# Swiip_REV_A1.net
KiCad netlist of a schematic drawn in EAGLE
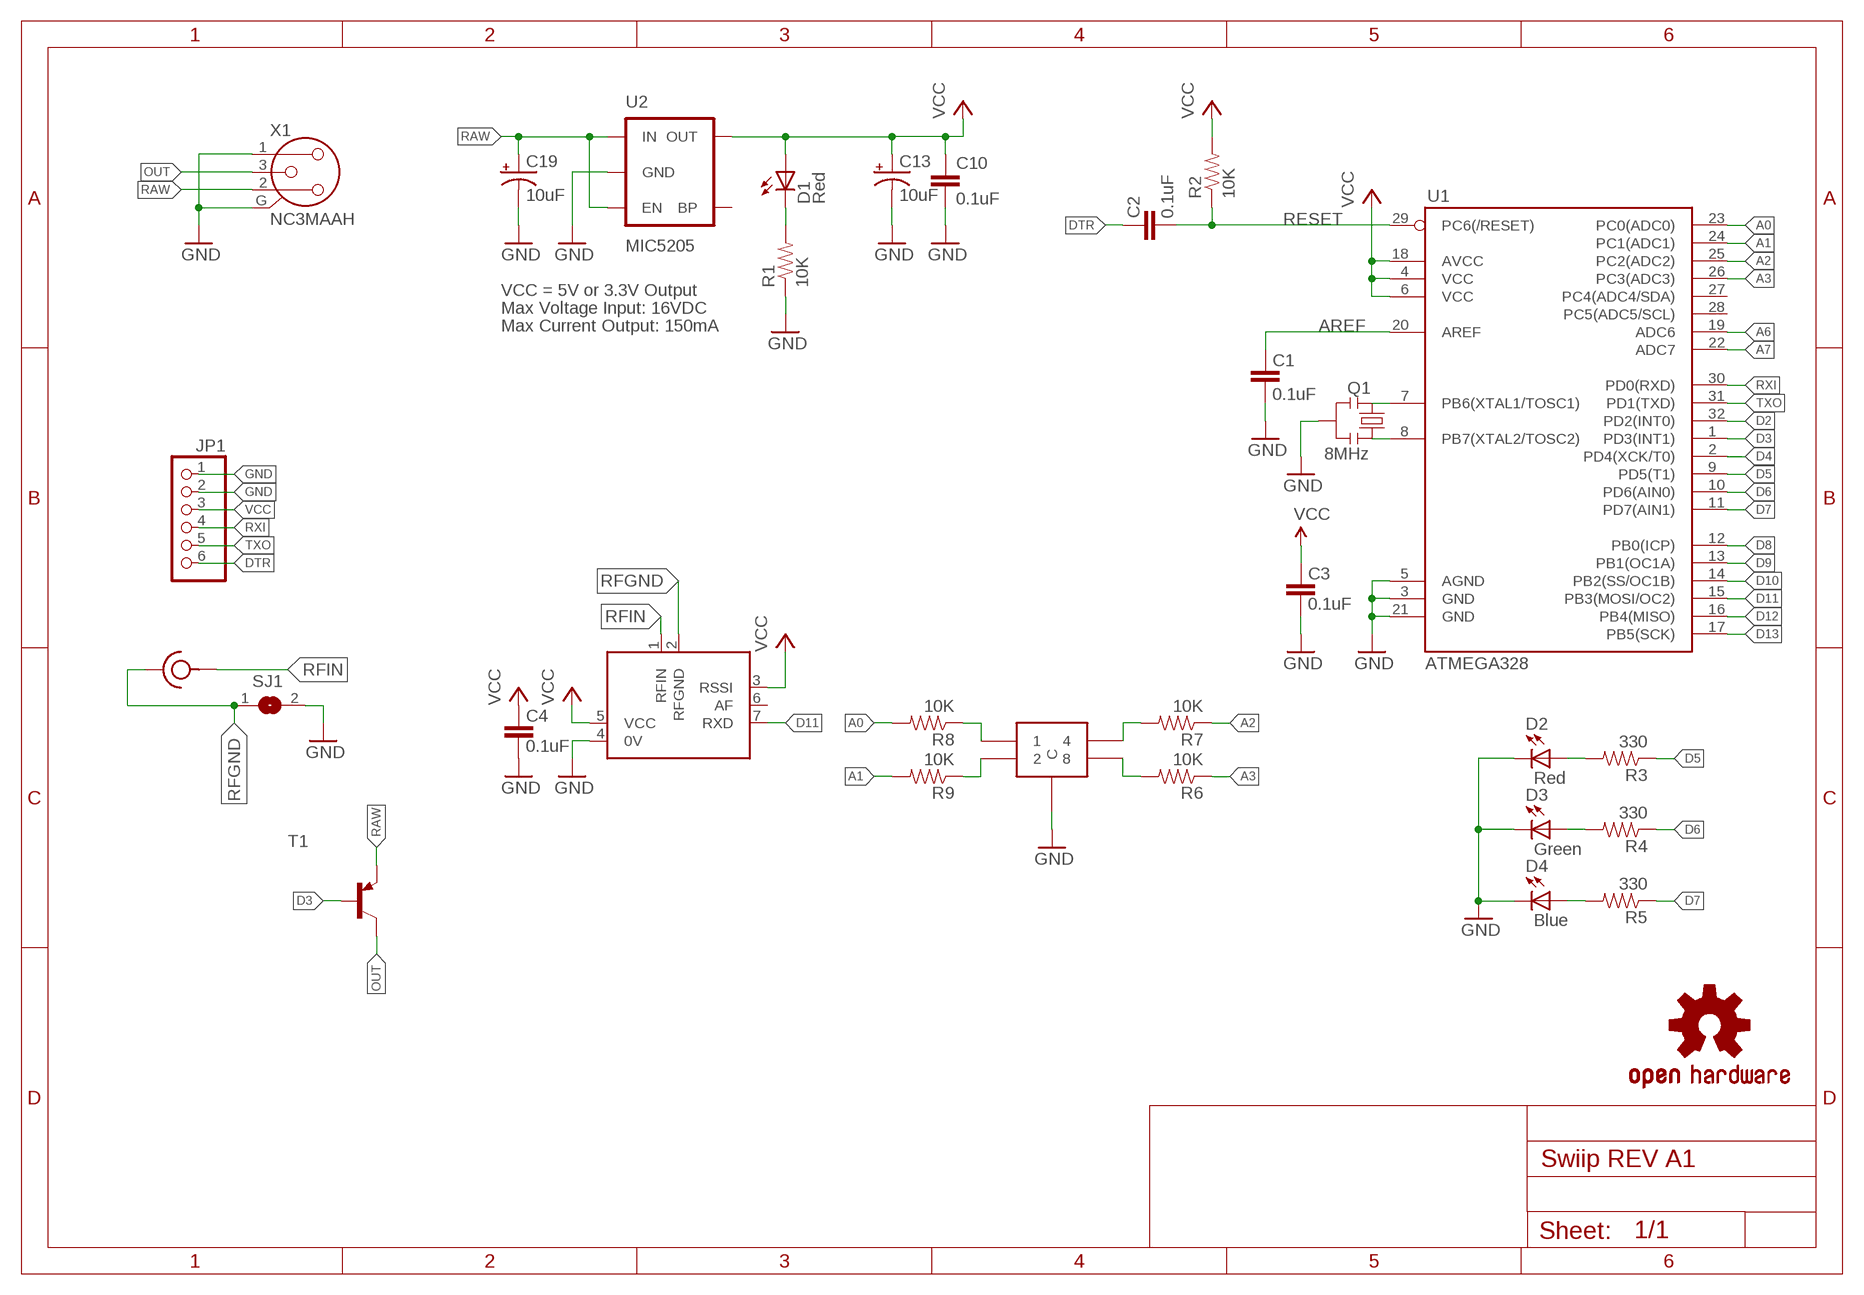
[diagram p0: schematic, sheet 1]

(export (version "E")
  (design (tool "Eeschema 10.0.6"))
  (components
    (comp (ref "C1")
      (value "0.1uF")
      (footprint "eagle-import:0603-CAP")
      (fields (field (name "MF") "MULTICOMP") (field (name "MPN") "MC0603F104Z160CT"))
      (libsource (lib "eagle-import") (part "CAP0603-CAP"))
    )
    (comp (ref "C2")
      (value "0.1uF")
      (footprint "eagle-import:0603-CAP")
      (fields (field (name "MF") "MULTICOMP") (field (name "MPN") "MC0603F104Z160CT"))
      (libsource (lib "eagle-import") (part "CAP0603-CAP"))
    )
    (comp (ref "C3")
      (value "0.1uF")
      (footprint "eagle-import:0603-CAP")
      (fields (field (name "MF") "MULTICOMP") (field (name "MPN") "MC0603F104Z160CT"))
      (libsource (lib "eagle-import") (part "CAP0603-CAP"))
    )
    (comp (ref "C4")
      (value "0.1uF")
      (footprint "eagle-import:0603-CAP")
      (fields (field (name "MF") "MULTICOMP") (field (name "MPN") "MC0603F104Z160CT"))
      (libsource (lib "eagle-import") (part "CAP0603-CAP"))
    )
    (comp (ref "C10")
      (value "0.1uF")
      (footprint "eagle-import:0603-CAP")
      (fields (field (name "MF") "MULTICOMP") (field (name "MPN") "MC0603F104Z160CT"))
      (libsource (lib "eagle-import") (part "CAP0603-CAP"))
    )
    (comp (ref "C13")
      (value "10uF")
      (footprint "eagle-import:EIA3216")
      (fields (field (name "MF") "MULTICOMP") (field (name "MPN") "MCCTA106M006"))
      (libsource (lib "eagle-import") (part "CAP_POL1206"))
    )
    (comp (ref "C19")
      (value "10uF")
      (footprint "eagle-import:EIA3216")
      (fields (field (name "MF") "MULTICOMP") (field (name "MPN") "MCCTA106M006"))
      (libsource (lib "eagle-import") (part "CAP_POL1206"))
    )
    (comp (ref "D1")
      (value "Red")
      (footprint "eagle-import:0603-LED-ALT1")
      (fields (field (name "MF") "MULTICOMP") (field (name "MPN") "MCL-S290SRC"))
      (libsource (lib "eagle-import") (part "LED"))
    )
    (comp (ref "D2")
      (value "Red")
      (footprint "eagle-import:0603-LED-ALT1")
      (fields (field (name "MF") "MULTICOMP") (field (name "MPN") "703-0109"))
      (libsource (lib "eagle-import") (part "LED"))
    )
    (comp (ref "D3")
      (value "Green")
      (footprint "eagle-import:0603-LED-ALT1")
      (fields (field (name "MF") "MULTICOMP") (field (name "MPN") "703-0109"))
      (libsource (lib "eagle-import") (part "LED"))
    )
    (comp (ref "D4")
      (value "Blue")
      (footprint "eagle-import:0603-LED-ALT1")
      (fields (field (name "MF") "MULTICOMP") (field (name "MPN") "703-0109"))
      (libsource (lib "eagle-import") (part "LED"))
    )
    (comp (ref "JP1")
      (value "PINHD-1X6")
      (footprint "eagle-import:1X06")
      (fields (field (name "MF") "MULTICOMP") (field (name "MPN") "MC34751"))
      (libsource (lib "eagle-import") (part "PINHD-1X6"))
    )
    (comp (ref "Q1")
      (value "8MHz")
      (footprint "eagle-import:RESONATOR-SMD-1_1")
      (fields (field (name "MF") "MURATA") (field (name "MPN") "CSTCE8M00G55Z-R0"))
      (libsource (lib "eagle-import") (part "RESONATOR1{colon}1"))
    )
    (comp (ref "R1")
      (value "10K")
      (footprint "eagle-import:0603-RES")
      (fields (field (name "MF") "MULTICOMP") (field (name "MPN") "MCHP03W8F1002T5E"))
      (libsource (lib "eagle-import") (part "RESISTOR0603-RES"))
    )
    (comp (ref "R2")
      (value "10K")
      (footprint "eagle-import:0603-RES")
      (fields (field (name "MF") "MULTICOMP") (field (name "MPN") "MCHP03W8F1002T5E"))
      (libsource (lib "eagle-import") (part "RESISTOR0603-RES"))
    )
    (comp (ref "R3")
      (value "330")
      (footprint "eagle-import:0603-RES")
      (fields (field (name "MF") "MULTICOMP") (field (name "MPN") "MCWR06X3300FTL"))
      (libsource (lib "eagle-import") (part "RESISTOR0603-RES"))
    )
    (comp (ref "R4")
      (value "330")
      (footprint "eagle-import:0603-RES")
      (fields (field (name "MF") "MULTICOMP") (field (name "MPN") "MCWR06X3300FTL"))
      (libsource (lib "eagle-import") (part "RESISTOR0603-RES"))
    )
    (comp (ref "R5")
      (value "330")
      (footprint "eagle-import:0603-RES")
      (fields (field (name "MF") "MULTICOMP") (field (name "MPN") "MCWR06X3300FTL"))
      (libsource (lib "eagle-import") (part "RESISTOR0603-RES"))
    )
    (comp (ref "R6")
      (value "10K")
      (footprint "eagle-import:0603-RES")
      (fields (field (name "MF") "MULTICOMP") (field (name "MPN") "MCHP03W8F1002T5E"))
      (libsource (lib "eagle-import") (part "RESISTOR0603-RES"))
    )
    (comp (ref "R7")
      (value "10K")
      (footprint "eagle-import:0603-RES")
      (fields (field (name "MF") "MULTICOMP") (field (name "MPN") "MCHP03W8F1002T5E"))
      (libsource (lib "eagle-import") (part "RESISTOR0603-RES"))
    )
    (comp (ref "R8")
      (value "10K")
      (footprint "eagle-import:0603-RES")
      (fields (field (name "MF") "MULTICOMP") (field (name "MPN") "MCHP03W8F1002T5E"))
      (libsource (lib "eagle-import") (part "RESISTOR0603-RES"))
    )
    (comp (ref "R9")
      (value "10K")
      (footprint "eagle-import:0603-RES")
      (fields (field (name "MF") "MULTICOMP") (field (name "MPN") "MCHP03W8F1002T5E"))
      (libsource (lib "eagle-import") (part "RESISTOR0603-RES"))
    )
    (comp (ref "RF1")
      (value "132203")
      (footprint "eagle-import:132203")
      (fields (field (name "MF") "AMPHENOL CONNEX"))
      (libsource (lib "eagle-import") (part "132203"))
    )
    (comp (ref "SJ1") (value "SJ") (footprint "eagle-import:SJ") (libsource (lib "eagle-import") (part "SJ")))
    (comp (ref "T1")
      (value "-PNP-SOT23-BCE")
      (footprint "eagle-import:SOT23-BCE")
      (fields (field (name "MF") "NXP") (field (name "MPN") "BC807-25"))
      (libsource (lib "eagle-import") (part "-PNP-SOT23-BCE"))
    )
    (comp (ref "U$1")
      (value "PT65-101-L508")
      (footprint "eagle-import:PT65-101-L508")
      (fields (field (name "MF") "APEM"))
      (libsource (lib "eagle-import") (part "PT65-101-?L508"))
    )
    (comp (ref "U$2")
      (value "RX2A-433-64")
      (footprint "eagle-import:RX2A")
      (fields (field (name "MF") "RADIOMETRIX"))
      (libsource (lib "eagle-import") (part "RX2A-433-64"))
    )
    (comp (ref "U$3")
      (value "OSHW-LOGOS")
      (footprint "eagle-import:OSHW-LOGO-S")
      (libsource (lib "eagle-import") (part "OSHW-LOGOS"))
    )
    (comp (ref "U1")
      (value "ATMEGA328")
      (footprint "eagle-import:TQFP32-08")
      (fields (field (name "MF") "ATMEL") (field (name "MPN") "ATMEGA328-AUR"))
      (libsource (lib "eagle-import") (part "ATMEGA168"))
    )
    (comp (ref "U2")
      (value "MIC5205")
      (footprint "eagle-import:SOT23-5")
      (fields (field (name "MF") "MICREL SEMICONDUCTOR") (field (name "MPN") "MIC5205-3.0YM5 TR"))
      (libsource (lib "eagle-import") (part "V_REG_LDOSMD"))
    )
    (comp (ref "X1")
      (value "NC3MAAH")
      (footprint "eagle-import:NC3MAH")
      (fields (field (name "MF") "NEUTRIK"))
      (libsource (lib "eagle-import") (part "NC3MAAH"))
    )
  )
  (nets
    (net (code "1") (name "/AREF") (class "Default")
      (node (ref "C1") (pin "2") (pinfunction "2_2") (pintype "passive"))
      (node (ref "U1") (pin "20") (pinfunction "AREF_20") (pintype "bidirectional"))
    )
    (net (code "2") (name "/RESET") (class "Default")
      (node (ref "C2") (pin "1") (pinfunction "1_1") (pintype "passive"))
      (node (ref "R2") (pin "1") (pinfunction "1_1") (pintype "passive"))
      (node (ref "U1") (pin "29") (pinfunction "PC6(/RESET)_29") (pintype "bidirectional"))
    )
    (net (code "3") (name "A0") (class "Default")
      (node (ref "R8") (pin "2") (pinfunction "2_2") (pintype "passive"))
      (node (ref "U1") (pin "23") (pinfunction "PC0(ADC0)_23") (pintype "bidirectional"))
    )
    (net (code "4") (name "A1") (class "Default")
      (node (ref "R9") (pin "2") (pinfunction "2_2") (pintype "passive"))
      (node (ref "U1") (pin "24") (pinfunction "PC1(ADC1)_24") (pintype "bidirectional"))
    )
    (net (code "5") (name "A2") (class "Default")
      (node (ref "R7") (pin "1") (pinfunction "1_1") (pintype "passive"))
      (node (ref "U1") (pin "25") (pinfunction "PC2(ADC2)_25") (pintype "bidirectional"))
    )
    (net (code "6") (name "A3") (class "Default")
      (node (ref "R6") (pin "1") (pinfunction "1_1") (pintype "passive"))
      (node (ref "U1") (pin "26") (pinfunction "PC3(ADC3)_26") (pintype "bidirectional"))
    )
    (net (code "7") (name "A6") (class "Default")
      (node (ref "U1") (pin "19") (pinfunction "ADC6_19") (pintype "bidirectional"))
    )
    (net (code "8") (name "A7") (class "Default")
      (node (ref "U1") (pin "22") (pinfunction "ADC7_22") (pintype "bidirectional"))
    )
    (net (code "9") (name "D2") (class "Default")
      (node (ref "U1") (pin "32") (pinfunction "PD2(INT0)_32") (pintype "bidirectional"))
    )
    (net (code "10") (name "D3") (class "Default")
      (node (ref "T1") (pin "B") (pinfunction "B_B") (pintype "passive"))
      (node (ref "U1") (pin "1") (pinfunction "PD3(INT1)_1") (pintype "bidirectional"))
    )
    (net (code "11") (name "D4") (class "Default")
      (node (ref "U1") (pin "2") (pinfunction "PD4(XCK/T0)_2") (pintype "bidirectional"))
    )
    (net (code "12") (name "D5") (class "Default")
      (node (ref "R3") (pin "1") (pinfunction "1_1") (pintype "passive"))
      (node (ref "U1") (pin "9") (pinfunction "PD5(T1)_9") (pintype "bidirectional"))
    )
    (net (code "13") (name "D6") (class "Default")
      (node (ref "R4") (pin "1") (pinfunction "1_1") (pintype "passive"))
      (node (ref "U1") (pin "10") (pinfunction "PD6(AIN0)_10") (pintype "bidirectional"))
    )
    (net (code "14") (name "D7") (class "Default")
      (node (ref "R5") (pin "1") (pinfunction "1_1") (pintype "passive"))
      (node (ref "U1") (pin "11") (pinfunction "PD7(AIN1)_11") (pintype "bidirectional"))
    )
    (net (code "15") (name "D8") (class "Default")
      (node (ref "U1") (pin "12") (pinfunction "PB0(ICP)_12") (pintype "bidirectional"))
    )
    (net (code "16") (name "D9") (class "Default")
      (node (ref "U1") (pin "13") (pinfunction "PB1(OC1A)_13") (pintype "bidirectional"))
    )
    (net (code "17") (name "D10") (class "Default")
      (node (ref "U1") (pin "14") (pinfunction "PB2(SS/OC1B)_14") (pintype "bidirectional"))
    )
    (net (code "18") (name "D11") (class "Default")
      (node (ref "U$2") (pin "7") (pinfunction "RXD_7") (pintype "output"))
      (node (ref "U1") (pin "15") (pinfunction "PB3(MOSI/OC2)_15") (pintype "bidirectional"))
    )
    (net (code "19") (name "D12") (class "Default")
      (node (ref "U1") (pin "16") (pinfunction "PB4(MISO)_16") (pintype "bidirectional"))
    )
    (net (code "20") (name "D13") (class "Default")
      (node (ref "U1") (pin "17") (pinfunction "PB5(SCK)_17") (pintype "bidirectional"))
    )
    (net (code "21") (name "DTR") (class "Default")
      (node (ref "C2") (pin "2") (pinfunction "2_2") (pintype "passive"))
      (node (ref "JP1") (pin "6") (pinfunction "6_6") (pintype "passive"))
    )
    (net (code "22") (name "GND") (class "Default")
      (node (ref "C1") (pin "1") (pinfunction "1_1") (pintype "passive"))
      (node (ref "C10") (pin "2") (pinfunction "2_2") (pintype "passive"))
      (node (ref "C13") (pin "C") (pinfunction "-_C") (pintype "passive"))
      (node (ref "C19") (pin "C") (pinfunction "-_C") (pintype "passive"))
      (node (ref "C3") (pin "1") (pinfunction "1_1") (pintype "passive"))
      (node (ref "C4") (pin "1") (pinfunction "1_1") (pintype "passive"))
      (node (ref "D2") (pin "C") (pinfunction "C_C") (pintype "passive"))
      (node (ref "D3") (pin "C") (pinfunction "C_C") (pintype "passive"))
      (node (ref "D4") (pin "C") (pinfunction "C_C") (pintype "passive"))
      (node (ref "JP1") (pin "1") (pinfunction "1_1") (pintype "passive"))
      (node (ref "JP1") (pin "2") (pinfunction "2_2") (pintype "passive"))
      (node (ref "Q1") (pin "2") (pinfunction "2_2") (pintype "passive"))
      (node (ref "R1") (pin "1") (pinfunction "1_1") (pintype "passive"))
      (node (ref "SJ1") (pin "2") (pinfunction "2_2") (pintype "passive"))
      (node (ref "U$1") (pin "C1") (pinfunction "C_C1") (pintype "bidirectional"))
      (node (ref "U$1") (pin "C2") (pinfunction "C_C2") (pintype "bidirectional"))
      (node (ref "U$2") (pin "4") (pinfunction "0V_4") (pintype "power_in"))
      (node (ref "U1") (pin "21") (pinfunction "GND_21") (pintype "bidirectional"))
      (node (ref "U1") (pin "3") (pinfunction "GND_3") (pintype "bidirectional"))
      (node (ref "U1") (pin "5") (pinfunction "AGND_5") (pintype "bidirectional"))
      (node (ref "U2") (pin "2") (pinfunction "GND_2") (pintype "input"))
      (node (ref "X1") (pin "1") (pinfunction "1_1") (pintype "passive"))
      (node (ref "X1") (pin "G") (pinfunction "G_G") (pintype "passive"))
    )
    (net (code "23") (name "Net-(D1-PadC)") (class "Default")
      (node (ref "D1") (pin "C") (pinfunction "C_C") (pintype "passive"))
      (node (ref "R1") (pin "2") (pinfunction "2_2") (pintype "passive"))
    )
    (net (code "24") (name "Net-(D2-PadA)") (class "Default")
      (node (ref "D2") (pin "A") (pinfunction "A_A") (pintype "passive"))
      (node (ref "R3") (pin "2") (pinfunction "2_2") (pintype "passive"))
    )
    (net (code "25") (name "Net-(D3-PadA)") (class "Default")
      (node (ref "D3") (pin "A") (pinfunction "A_A") (pintype "passive"))
      (node (ref "R4") (pin "2") (pinfunction "2_2") (pintype "passive"))
    )
    (net (code "26") (name "Net-(D4-PadA)") (class "Default")
      (node (ref "D4") (pin "A") (pinfunction "A_A") (pintype "passive"))
      (node (ref "R5") (pin "2") (pinfunction "2_2") (pintype "passive"))
    )
    (net (code "27") (name "Net-(R6-Pad2)") (class "Default")
      (node (ref "R6") (pin "2") (pinfunction "2_2") (pintype "passive"))
      (node (ref "U$1") (pin "8") (pinfunction "8_8") (pintype "bidirectional"))
    )
    (net (code "28") (name "Net-(R7-Pad2)") (class "Default")
      (node (ref "R7") (pin "2") (pinfunction "2_2") (pintype "passive"))
      (node (ref "U$1") (pin "4") (pinfunction "4_4") (pintype "bidirectional"))
    )
    (net (code "29") (name "Net-(R8-Pad1)") (class "Default")
      (node (ref "R8") (pin "1") (pinfunction "1_1") (pintype "passive"))
      (node (ref "U$1") (pin "1") (pinfunction "1_1") (pintype "bidirectional"))
    )
    (net (code "30") (name "Net-(R9-Pad1)") (class "Default")
      (node (ref "R9") (pin "1") (pinfunction "1_1") (pintype "passive"))
      (node (ref "U$1") (pin "2") (pinfunction "2_2") (pintype "bidirectional"))
    )
    (net (code "31") (name "Net-(U1-PB6(XTAL1{slash}TOSC1))") (class "Default")
      (node (ref "Q1") (pin "1") (pinfunction "1_1") (pintype "passive"))
      (node (ref "U1") (pin "7") (pinfunction "PB6(XTAL1/TOSC1)_7") (pintype "bidirectional"))
    )
    (net (code "32") (name "Net-(U1-PB7(XTAL2{slash}TOSC2))") (class "Default")
      (node (ref "Q1") (pin "3") (pinfunction "3_3") (pintype "passive"))
      (node (ref "U1") (pin "8") (pinfunction "PB7(XTAL2/TOSC2)_8") (pintype "bidirectional"))
    )
    (net (code "33") (name "OUT") (class "Default")
      (node (ref "T1") (pin "C") (pinfunction "C_C") (pintype "passive"))
      (node (ref "X1") (pin "3") (pinfunction "3_3") (pintype "passive"))
    )
    (net (code "34") (name "RAW") (class "Default")
      (node (ref "C19") (pin "A") (pinfunction "+_A") (pintype "passive"))
      (node (ref "T1") (pin "E") (pinfunction "E_E") (pintype "passive"))
      (node (ref "U2") (pin "1") (pinfunction "IN_1") (pintype "input"))
      (node (ref "U2") (pin "3") (pinfunction "EN_3") (pintype "input"))
      (node (ref "X1") (pin "2") (pinfunction "2_2") (pintype "passive"))
    )
    (net (code "35") (name "RFGND") (class "Default")
      (node (ref "RF1") (pin "G1") (pinfunction "GND_G1") (pintype "bidirectional"))
      (node (ref "RF1") (pin "G2") (pinfunction "GND_G2") (pintype "bidirectional"))
      (node (ref "RF1") (pin "G3") (pinfunction "GND_G3") (pintype "bidirectional"))
      (node (ref "RF1") (pin "G4") (pinfunction "GND_G4") (pintype "bidirectional"))
      (node (ref "SJ1") (pin "1") (pinfunction "1_1") (pintype "passive"))
      (node (ref "U$2") (pin "2") (pinfunction "RFGND_2") (pintype "input"))
    )
    (net (code "36") (name "RFIN") (class "Default")
      (node (ref "RF1") (pin "P") (pinfunction "RF_P") (pintype "bidirectional"))
      (node (ref "U$2") (pin "1") (pinfunction "RFIN_1") (pintype "input"))
    )
    (net (code "37") (name "RXI") (class "Default")
      (node (ref "JP1") (pin "4") (pinfunction "4_4") (pintype "passive"))
      (node (ref "U1") (pin "30") (pinfunction "PD0(RXD)_30") (pintype "bidirectional"))
    )
    (net (code "38") (name "TXO") (class "Default")
      (node (ref "JP1") (pin "5") (pinfunction "5_5") (pintype "passive"))
      (node (ref "U1") (pin "31") (pinfunction "PD1(TXD)_31") (pintype "bidirectional"))
    )
    (net (code "39") (name "VCC") (class "Default")
      (node (ref "C10") (pin "1") (pinfunction "1_1") (pintype "passive"))
      (node (ref "C13") (pin "A") (pinfunction "+_A") (pintype "passive"))
      (node (ref "C3") (pin "2") (pinfunction "2_2") (pintype "passive"))
      (node (ref "C4") (pin "2") (pinfunction "2_2") (pintype "passive"))
      (node (ref "D1") (pin "A") (pinfunction "A_A") (pintype "passive"))
      (node (ref "JP1") (pin "3") (pinfunction "3_3") (pintype "passive"))
      (node (ref "R2") (pin "2") (pinfunction "2_2") (pintype "passive"))
      (node (ref "U$2") (pin "3") (pinfunction "RSSI_3") (pintype "output"))
      (node (ref "U$2") (pin "5") (pinfunction "VCC_5") (pintype "power_in"))
      (node (ref "U1") (pin "18") (pinfunction "AVCC_18") (pintype "bidirectional"))
      (node (ref "U1") (pin "4") (pinfunction "VCC_4") (pintype "bidirectional"))
      (node (ref "U1") (pin "6") (pinfunction "VCC_6") (pintype "bidirectional"))
      (node (ref "U2") (pin "5") (pinfunction "OUT_5") (pintype "passive"))
    )
    (net (code "40") (name "unconnected-(U$2-AF-Pad6)") (class "Default")
      (node (ref "U$2") (pin "6") (pinfunction "AF_6") (pintype "output"))
    )
    (net (code "41") (name "unconnected-(U1-PC4(ADC4{slash}SDA)-Pad27)") (class "Default")
      (node (ref "U1") (pin "27") (pinfunction "PC4(ADC4/SDA)_27") (pintype "bidirectional"))
    )
    (net (code "42") (name "unconnected-(U1-PC5(ADC5{slash}SCL)-Pad28)") (class "Default")
      (node (ref "U1") (pin "28") (pinfunction "PC5(ADC5/SCL)_28") (pintype "bidirectional"))
    )
    (net (code "43") (name "unconnected-(U2-BP-Pad4)") (class "Default")
      (node (ref "U2") (pin "4") (pinfunction "BP_4") (pintype "input"))
    )
  )
)
